# CW_Encoder.net
KiCad netlist of a schematic drawn in EAGLE
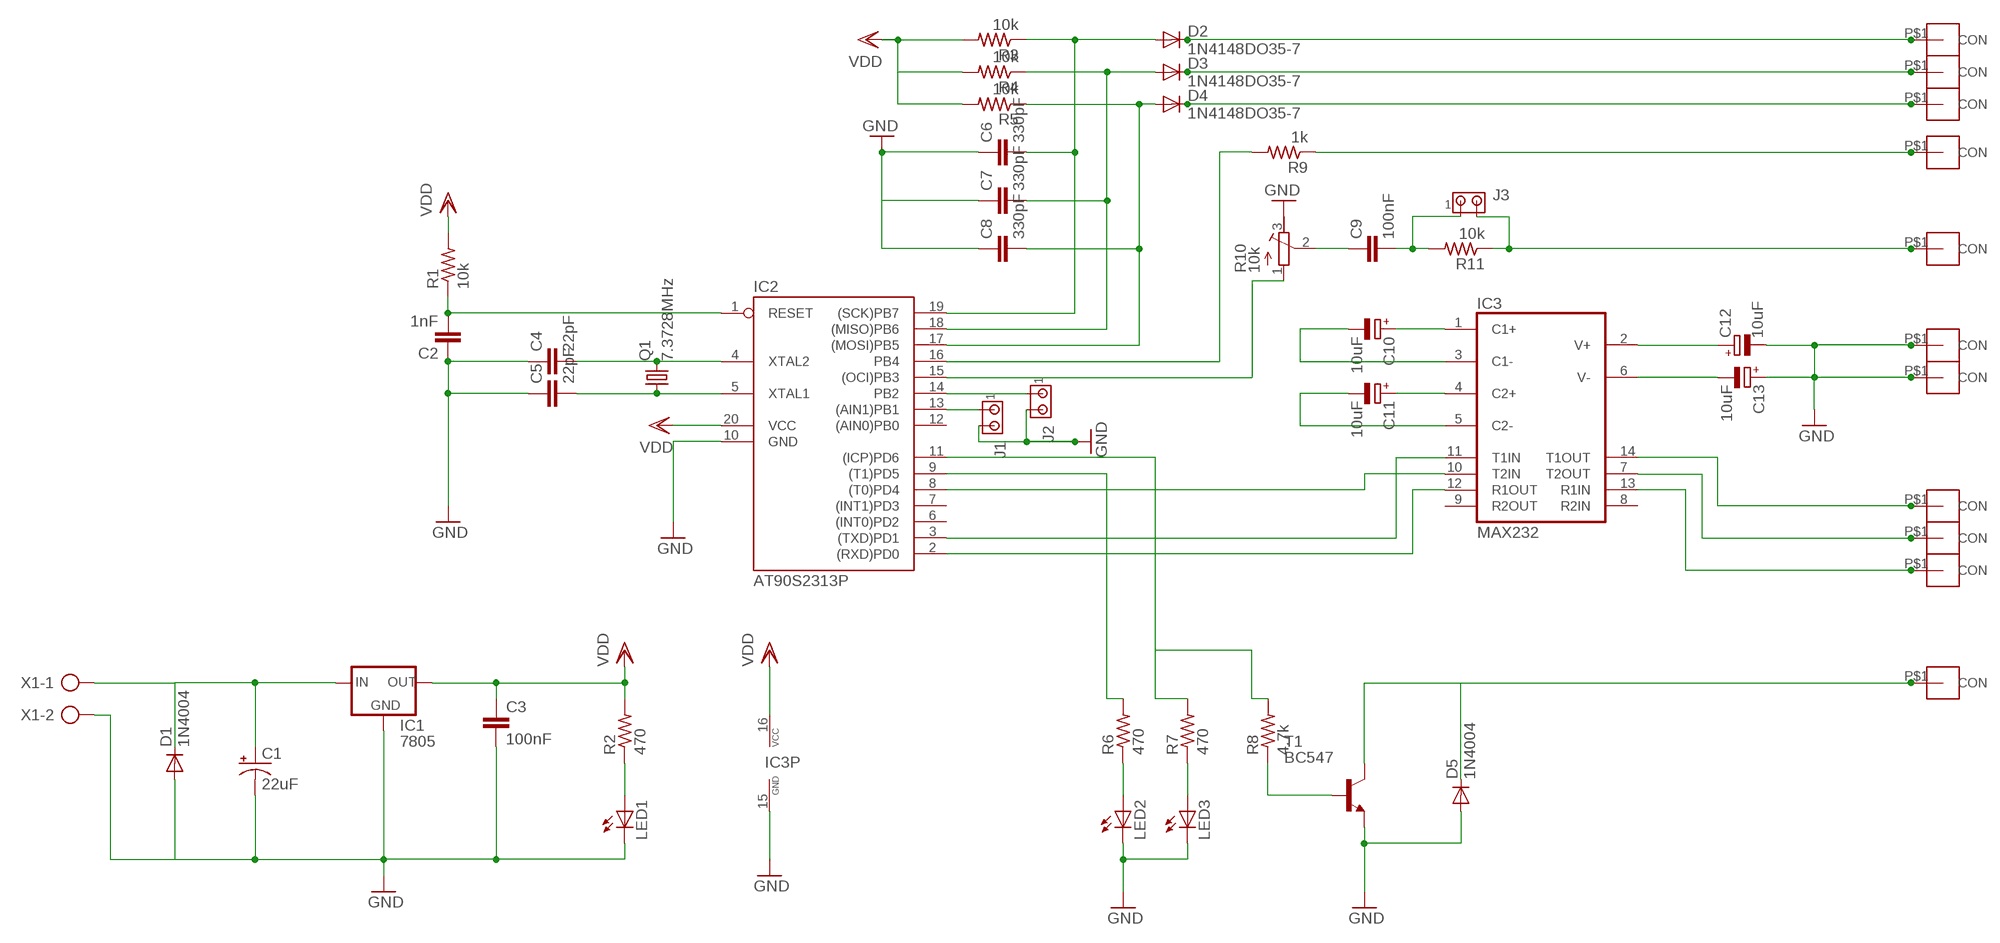
[diagram p0: schematic, sheet 2]

(export (version "E")
  (design (tool "Eeschema 10.0.6"))
  (components
    (comp (ref "C1")
      (value "22uF")
      (footprint "eagle-import:E2,5-4R")
      (libsource (lib "eagle-import") (part "CPOL-USE2.5-5V"))
    )
    (comp (ref "C2")
      (value "1nF")
      (footprint "eagle-import:C025-024X044")
      (libsource (lib "eagle-import") (part "C-EU025-024X044"))
    )
    (comp (ref "C3")
      (value "100nF")
      (footprint "eagle-import:C025-024X044")
      (libsource (lib "eagle-import") (part "C-EU025-024X044"))
    )
    (comp (ref "C4")
      (value "22pF")
      (footprint "eagle-import:C025-024X044")
      (libsource (lib "eagle-import") (part "C-EU025-024X044"))
    )
    (comp (ref "C5")
      (value "22pF")
      (footprint "eagle-import:C025-024X044")
      (libsource (lib "eagle-import") (part "C-EU025-024X044"))
    )
    (comp (ref "C6")
      (value "330pF")
      (footprint "eagle-import:C025-024X044")
      (libsource (lib "eagle-import") (part "C-EU025-024X044"))
    )
    (comp (ref "C7")
      (value "330pF")
      (footprint "eagle-import:C025-024X044")
      (libsource (lib "eagle-import") (part "C-EU025-024X044"))
    )
    (comp (ref "C8")
      (value "330pF")
      (footprint "eagle-import:C025-024X044")
      (libsource (lib "eagle-import") (part "C-EU025-024X044"))
    )
    (comp (ref "C9")
      (value "100nF")
      (footprint "eagle-import:C025-024X044")
      (libsource (lib "eagle-import") (part "C-EU025-024X044"))
    )
    (comp (ref "C10")
      (value "10uF")
      (footprint "eagle-import:B45181A")
      (libsource (lib "eagle-import") (part "CPOL-EUB45181A"))
    )
    (comp (ref "C11")
      (value "10uF")
      (footprint "eagle-import:B45181A")
      (libsource (lib "eagle-import") (part "CPOL-EUB45181A"))
    )
    (comp (ref "C12")
      (value "10uF")
      (footprint "eagle-import:B45181A")
      (libsource (lib "eagle-import") (part "CPOL-EUB45181A"))
    )
    (comp (ref "C13")
      (value "10uF")
      (footprint "eagle-import:B45181A")
      (libsource (lib "eagle-import") (part "CPOL-EUB45181A"))
    )
    (comp (ref "CTS")
      (value "CON1")
      (footprint "eagle-import:CON1")
      (libsource (lib "eagle-import") (part "CON1"))
    )
    (comp (ref "CWOUT")
      (value "CON1")
      (footprint "eagle-import:CON1")
      (libsource (lib "eagle-import") (part "CON1"))
    )
    (comp (ref "D1")
      (value "1N4004")
      (footprint "eagle-import:DO41-10")
      (libsource (lib "eagle-import") (part "1N4004"))
    )
    (comp (ref "D2")
      (value "1N4148DO35-7")
      (footprint "eagle-import:DO35-7")
      (libsource (lib "eagle-import") (part "1N4148DO35-7"))
    )
    (comp (ref "D3")
      (value "1N4148DO35-7")
      (footprint "eagle-import:DO35-7")
      (libsource (lib "eagle-import") (part "1N4148DO35-7"))
    )
    (comp (ref "D4")
      (value "1N4148DO35-7")
      (footprint "eagle-import:DO35-7")
      (libsource (lib "eagle-import") (part "1N4148DO35-7"))
    )
    (comp (ref "D5")
      (value "1N4004")
      (footprint "eagle-import:DO41-10")
      (libsource (lib "eagle-import") (part "1N4004"))
    )
    (comp (ref "GND")
      (value "CON1")
      (footprint "eagle-import:CON1")
      (libsource (lib "eagle-import") (part "CON1"))
    )
    (comp (ref "GND_")
      (value "CON1")
      (footprint "eagle-import:CON1")
      (libsource (lib "eagle-import") (part "CON1"))
    )
    (comp (ref "IC1")
      (value "7805")
      (footprint "eagle-import:78XXL")
      (libsource (lib "eagle-import") (part "78XXL"))
    )
    (comp (ref "IC2")
      (value "AT90S2313P")
      (footprint "eagle-import:DIL20")
      (libsource (lib "eagle-import") (part "AT90S2313P"))
    )
    (comp (ref "IC3")
      (value "MAX232")
      (footprint "eagle-import:DIL16")
      (fields (field (name "MF") "MAXIM") (field (name "MPN") "MAX232ACPE+"))
      (libsource (lib "eagle-import") (part "MAX232"))
    )
    (comp (ref "IN1")
      (value "CON1")
      (footprint "eagle-import:CON1")
      (libsource (lib "eagle-import") (part "CON1"))
    )
    (comp (ref "IN2")
      (value "CON1")
      (footprint "eagle-import:CON1")
      (libsource (lib "eagle-import") (part "CON1"))
    )
    (comp (ref "J1")
      (value "MTA02-100")
      (footprint "eagle-import:10X02MTA")
      (libsource (lib "eagle-import") (part "MTA02-100"))
    )
    (comp (ref "J2")
      (value "MTA02-100")
      (footprint "eagle-import:10X02MTA")
      (libsource (lib "eagle-import") (part "MTA02-100"))
    )
    (comp (ref "J3")
      (value "MTA02-100")
      (footprint "eagle-import:10X02MTA")
      (libsource (lib "eagle-import") (part "MTA02-100"))
    )
    (comp (ref "LED1")
      (value "LED5MM")
      (footprint "eagle-import:LED5MM")
      (libsource (lib "eagle-import") (part "LED5MM"))
    )
    (comp (ref "LED2")
      (value "LED5MM")
      (footprint "eagle-import:LED5MM")
      (libsource (lib "eagle-import") (part "LED5MM"))
    )
    (comp (ref "LED3")
      (value "LED5MM")
      (footprint "eagle-import:LED5MM")
      (libsource (lib "eagle-import") (part "LED5MM"))
    )
    (comp (ref "POSAGOUT")
      (value "CON1")
      (footprint "eagle-import:CON1")
      (libsource (lib "eagle-import") (part "CON1"))
    )
    (comp (ref "PTT")
      (value "CON1")
      (footprint "eagle-import:CON1")
      (libsource (lib "eagle-import") (part "CON1"))
    )
    (comp (ref "Q1")
      (value "7.3728MHz")
      (footprint "eagle-import:HC49_S")
      (libsource (lib "eagle-import") (part "CRYSTALHC49S"))
    )
    (comp (ref "R1")
      (value "10k")
      (footprint "eagle-import:0204_7")
      (libsource (lib "eagle-import") (part "R-US_0204/7"))
    )
    (comp (ref "R2")
      (value "470")
      (footprint "eagle-import:0204_7")
      (libsource (lib "eagle-import") (part "R-US_0204/7"))
    )
    (comp (ref "R3")
      (value "10k")
      (footprint "eagle-import:0204_7")
      (libsource (lib "eagle-import") (part "R-US_0204/7"))
    )
    (comp (ref "R4")
      (value "10k")
      (footprint "eagle-import:0204_7")
      (libsource (lib "eagle-import") (part "R-US_0204/7"))
    )
    (comp (ref "R5")
      (value "10k")
      (footprint "eagle-import:0204_7")
      (libsource (lib "eagle-import") (part "R-US_0204/7"))
    )
    (comp (ref "R6")
      (value "470")
      (footprint "eagle-import:0204_7")
      (libsource (lib "eagle-import") (part "R-US_0204/7"))
    )
    (comp (ref "R7")
      (value "470")
      (footprint "eagle-import:0204_7")
      (libsource (lib "eagle-import") (part "R-US_0204/7"))
    )
    (comp (ref "R8")
      (value "4.7k")
      (footprint "eagle-import:0204_7")
      (libsource (lib "eagle-import") (part "R-US_0204/7"))
    )
    (comp (ref "R9")
      (value "1k")
      (footprint "eagle-import:0204_7")
      (libsource (lib "eagle-import") (part "R-US_0204/7"))
    )
    (comp (ref "R10")
      (value "10k")
      (footprint "eagle-import:RTRIM3339P")
      (libsource (lib "eagle-import") (part "R-TRIMM3339P"))
    )
    (comp (ref "R11")
      (value "10k")
      (footprint "eagle-import:0204_7")
      (libsource (lib "eagle-import") (part "R-US_0204/7"))
    )
    (comp (ref "T1")
      (value "BC547")
      (footprint "eagle-import:TO92")
      (libsource (lib "eagle-import") (part "BC547"))
    )
    (comp (ref "TX")
      (value "tx")
      (footprint "eagle-import:CON1")
      (libsource (lib "eagle-import") (part "CON1"))
    )
    (comp (ref "TXD")
      (value "CON1")
      (footprint "eagle-import:CON1")
      (libsource (lib "eagle-import") (part "CON1"))
    )
    (comp (ref "U$1")
      (value "CON1")
      (footprint "eagle-import:CON1")
      (libsource (lib "eagle-import") (part "CON1"))
    )
    (comp (ref "X1")
      (value "AK300/2")
      (footprint "eagle-import:AK300_2")
      (libsource (lib "eagle-import") (part "AK300/2"))
    )
  )
  (nets
    (net (code "1") (name "GND") (class "Default")
      (node (ref "C1") (pin "-") (pinfunction "-_-") (pintype "passive"))
      (node (ref "C12") (pin "-") (pinfunction "-_-") (pintype "passive"))
      (node (ref "C13") (pin "+") (pinfunction "+_+") (pintype "passive"))
      (node (ref "C2") (pin "1") (pinfunction "1_1") (pintype "passive"))
      (node (ref "C3") (pin "2") (pinfunction "2_2") (pintype "passive"))
      (node (ref "C4") (pin "1") (pinfunction "1_1") (pintype "passive"))
      (node (ref "C5") (pin "1") (pinfunction "1_1") (pintype "passive"))
      (node (ref "C6") (pin "1") (pinfunction "1_1") (pintype "passive"))
      (node (ref "C7") (pin "1") (pinfunction "1_1") (pintype "passive"))
      (node (ref "C8") (pin "1") (pinfunction "1_1") (pintype "passive"))
      (node (ref "D1") (pin "A") (pinfunction "A_A") (pintype "passive"))
      (node (ref "D5") (pin "A") (pinfunction "A_A") (pintype "passive"))
      (node (ref "GND") (pin "P$1") (pinfunction "CON_P$1") (pintype "bidirectional"))
      (node (ref "GND_") (pin "P$1") (pinfunction "CON_P$1") (pintype "bidirectional"))
      (node (ref "IC1") (pin "GND") (pinfunction "GND_GND") (pintype "input"))
      (node (ref "IC2") (pin "10") (pinfunction "GND_10") (pintype "power_in"))
      (node (ref "IC3") (pin "15") (pinfunction "GND_15") (pintype "power_in"))
      (node (ref "J1") (pin "2") (pinfunction "2_2") (pintype "passive"))
      (node (ref "J2") (pin "2") (pinfunction "2_2") (pintype "passive"))
      (node (ref "LED1") (pin "K") (pinfunction "C_K") (pintype "passive"))
      (node (ref "LED2") (pin "K") (pinfunction "C_K") (pintype "passive"))
      (node (ref "LED3") (pin "K") (pinfunction "C_K") (pintype "passive"))
      (node (ref "R10") (pin "3") (pinfunction "A_3") (pintype "passive"))
      (node (ref "T1") (pin "1") (pinfunction "E_1") (pintype "passive"))
      (node (ref "X1") (pin "2") (pinfunction "KL_2") (pintype "passive"))
    )
    (net (code "2") (name "Net-(C9-Pad2)") (class "Default")
      (node (ref "C9") (pin "2") (pinfunction "2_2") (pintype "passive"))
      (node (ref "J3") (pin "1") (pinfunction "1_1") (pintype "passive"))
      (node (ref "R11") (pin "2") (pinfunction "2_2") (pintype "passive"))
    )
    (net (code "3") (name "Net-(CTS-CON)") (class "Default")
      (node (ref "CTS") (pin "P$1") (pinfunction "CON_P$1") (pintype "bidirectional"))
      (node (ref "IC3") (pin "7") (pinfunction "T2OUT_7") (pintype "output"))
    )
    (net (code "4") (name "Net-(CWOUT-CON)") (class "Default")
      (node (ref "CWOUT") (pin "P$1") (pinfunction "CON_P$1") (pintype "bidirectional"))
      (node (ref "J3") (pin "2") (pinfunction "2_2") (pintype "passive"))
      (node (ref "R11") (pin "1") (pinfunction "1_1") (pintype "passive"))
    )
    (net (code "5") (name "Net-(IC2-(AIN1)PB1)") (class "Default")
      (node (ref "IC2") (pin "13") (pinfunction "(AIN1)PB1_13") (pintype "bidirectional"))
      (node (ref "J1") (pin "1") (pinfunction "1_1") (pintype "passive"))
    )
    (net (code "6") (name "Net-(IC2-(ICP)PD6)") (class "Default")
      (node (ref "IC2") (pin "11") (pinfunction "(ICP)PD6_11") (pintype "bidirectional"))
      (node (ref "R7") (pin "2") (pinfunction "2_2") (pintype "passive"))
      (node (ref "R8") (pin "2") (pinfunction "2_2") (pintype "passive"))
    )
    (net (code "7") (name "Net-(IC2-(MISO)PB6)") (class "Default")
      (node (ref "C7") (pin "2") (pinfunction "2_2") (pintype "passive"))
      (node (ref "D3") (pin "A") (pinfunction "A_A") (pintype "passive"))
      (node (ref "IC2") (pin "18") (pinfunction "(MISO)PB6_18") (pintype "bidirectional"))
      (node (ref "R4") (pin "1") (pinfunction "1_1") (pintype "passive"))
    )
    (net (code "8") (name "Net-(IC2-(MOSI)PB5)") (class "Default")
      (node (ref "C8") (pin "2") (pinfunction "2_2") (pintype "passive"))
      (node (ref "D4") (pin "A") (pinfunction "A_A") (pintype "passive"))
      (node (ref "IC2") (pin "17") (pinfunction "(MOSI)PB5_17") (pintype "bidirectional"))
      (node (ref "R5") (pin "1") (pinfunction "1_1") (pintype "passive"))
    )
    (net (code "9") (name "Net-(IC2-(OCI)PB3)") (class "Default")
      (node (ref "IC2") (pin "15") (pinfunction "(OCI)PB3_15") (pintype "bidirectional"))
      (node (ref "R10") (pin "1") (pinfunction "E_1") (pintype "passive"))
    )
    (net (code "10") (name "Net-(IC2-(RXD)PD0)") (class "Default")
      (node (ref "IC2") (pin "2") (pinfunction "(RXD)PD0_2") (pintype "bidirectional"))
      (node (ref "IC3") (pin "12") (pinfunction "R1OUT_12") (pintype "output"))
    )
    (net (code "11") (name "Net-(IC2-(SCK)PB7)") (class "Default")
      (node (ref "C6") (pin "2") (pinfunction "2_2") (pintype "passive"))
      (node (ref "D2") (pin "A") (pinfunction "A_A") (pintype "passive"))
      (node (ref "IC2") (pin "19") (pinfunction "(SCK)PB7_19") (pintype "bidirectional"))
      (node (ref "R3") (pin "1") (pinfunction "1_1") (pintype "passive"))
    )
    (net (code "12") (name "Net-(IC2-(T0)PD4)") (class "Default")
      (node (ref "IC2") (pin "8") (pinfunction "(T0)PD4_8") (pintype "bidirectional"))
      (node (ref "IC3") (pin "10") (pinfunction "T2IN_10") (pintype "input"))
    )
    (net (code "13") (name "Net-(IC2-(T1)PD5)") (class "Default")
      (node (ref "IC2") (pin "9") (pinfunction "(T1)PD5_9") (pintype "bidirectional"))
      (node (ref "R6") (pin "2") (pinfunction "2_2") (pintype "passive"))
    )
    (net (code "14") (name "Net-(IC2-(TXD)PD1)") (class "Default")
      (node (ref "IC2") (pin "3") (pinfunction "(TXD)PD1_3") (pintype "bidirectional"))
      (node (ref "IC3") (pin "11") (pinfunction "T1IN_11") (pintype "input"))
    )
    (net (code "15") (name "Net-(IC2-PB2)") (class "Default")
      (node (ref "IC2") (pin "14") (pinfunction "PB2_14") (pintype "bidirectional"))
      (node (ref "J2") (pin "1") (pinfunction "1_1") (pintype "passive"))
    )
    (net (code "16") (name "Net-(IC2-PB4)") (class "Default")
      (node (ref "IC2") (pin "16") (pinfunction "PB4_16") (pintype "bidirectional"))
      (node (ref "R9") (pin "2") (pinfunction "2_2") (pintype "passive"))
    )
    (net (code "17") (name "Net-(IC2-RESET)") (class "Default")
      (node (ref "C2") (pin "2") (pinfunction "2_2") (pintype "passive"))
      (node (ref "IC2") (pin "1") (pinfunction "RESET_1") (pintype "bidirectional"))
      (node (ref "R1") (pin "1") (pinfunction "1_1") (pintype "passive"))
    )
    (net (code "18") (name "Net-(IC2-XTAL1)") (class "Default")
      (node (ref "C5") (pin "2") (pinfunction "2_2") (pintype "passive"))
      (node (ref "IC2") (pin "5") (pinfunction "XTAL1_5") (pintype "bidirectional"))
      (node (ref "Q1") (pin "1") (pinfunction "1_1") (pintype "passive"))
    )
    (net (code "19") (name "Net-(IC2-XTAL2)") (class "Default")
      (node (ref "C4") (pin "2") (pinfunction "2_2") (pintype "passive"))
      (node (ref "IC2") (pin "4") (pinfunction "XTAL2_4") (pintype "bidirectional"))
      (node (ref "Q1") (pin "2") (pinfunction "2_2") (pintype "passive"))
    )
    (net (code "20") (name "Net-(IC3A-C1+)") (class "Default")
      (node (ref "C10") (pin "+") (pinfunction "+_+") (pintype "passive"))
      (node (ref "IC3") (pin "1") (pinfunction "C1+_1") (pintype "bidirectional"))
    )
    (net (code "21") (name "Net-(IC3A-C1-)") (class "Default")
      (node (ref "C10") (pin "-") (pinfunction "-_-") (pintype "passive"))
      (node (ref "IC3") (pin "3") (pinfunction "C1-_3") (pintype "bidirectional"))
    )
    (net (code "22") (name "Net-(IC3A-C2+)") (class "Default")
      (node (ref "C11") (pin "+") (pinfunction "+_+") (pintype "passive"))
      (node (ref "IC3") (pin "4") (pinfunction "C2+_4") (pintype "bidirectional"))
    )
    (net (code "23") (name "Net-(IC3A-C2-)") (class "Default")
      (node (ref "C11") (pin "-") (pinfunction "-_-") (pintype "passive"))
      (node (ref "IC3") (pin "5") (pinfunction "C2-_5") (pintype "bidirectional"))
    )
    (net (code "24") (name "Net-(IC3A-R1IN)") (class "Default")
      (node (ref "IC3") (pin "13") (pinfunction "R1IN_13") (pintype "input"))
      (node (ref "U$1") (pin "P$1") (pinfunction "CON_P$1") (pintype "bidirectional"))
    )
    (net (code "25") (name "Net-(IC3A-T1OUT)") (class "Default")
      (node (ref "IC3") (pin "14") (pinfunction "T1OUT_14") (pintype "output"))
      (node (ref "TXD") (pin "P$1") (pinfunction "CON_P$1") (pintype "bidirectional"))
    )
    (net (code "26") (name "Net-(IC3A-V+)") (class "Default")
      (node (ref "C12") (pin "+") (pinfunction "+_+") (pintype "passive"))
      (node (ref "IC3") (pin "2") (pinfunction "V+_2") (pintype "bidirectional"))
    )
    (net (code "27") (name "Net-(IC3A-V-)") (class "Default")
      (node (ref "C13") (pin "-") (pinfunction "-_-") (pintype "passive"))
      (node (ref "IC3") (pin "6") (pinfunction "V-_6") (pintype "bidirectional"))
    )
    (net (code "28") (name "Net-(IN1-CON)") (class "Default")
      (node (ref "D3") (pin "C") (pinfunction "C_C") (pintype "passive"))
      (node (ref "IN1") (pin "P$1") (pinfunction "CON_P$1") (pintype "bidirectional"))
    )
    (net (code "29") (name "Net-(IN2-CON)") (class "Default")
      (node (ref "D4") (pin "C") (pinfunction "C_C") (pintype "passive"))
      (node (ref "IN2") (pin "P$1") (pinfunction "CON_P$1") (pintype "bidirectional"))
    )
    (net (code "30") (name "Net-(LED1-PadA)") (class "Default")
      (node (ref "LED1") (pin "A") (pinfunction "A_A") (pintype "passive"))
      (node (ref "R2") (pin "1") (pinfunction "1_1") (pintype "passive"))
    )
    (net (code "31") (name "Net-(LED2-PadA)") (class "Default")
      (node (ref "LED2") (pin "A") (pinfunction "A_A") (pintype "passive"))
      (node (ref "R6") (pin "1") (pinfunction "1_1") (pintype "passive"))
    )
    (net (code "32") (name "Net-(LED3-PadA)") (class "Default")
      (node (ref "LED3") (pin "A") (pinfunction "A_A") (pintype "passive"))
      (node (ref "R7") (pin "1") (pinfunction "1_1") (pintype "passive"))
    )
    (net (code "33") (name "Net-(POSAGOUT-CON)") (class "Default")
      (node (ref "POSAGOUT") (pin "P$1") (pinfunction "CON_P$1") (pintype "bidirectional"))
      (node (ref "R9") (pin "1") (pinfunction "1_1") (pintype "passive"))
    )
    (net (code "34") (name "Net-(PTT-CON)") (class "Default")
      (node (ref "D5") (pin "C") (pinfunction "C_C") (pintype "passive"))
      (node (ref "PTT") (pin "P$1") (pinfunction "CON_P$1") (pintype "bidirectional"))
      (node (ref "T1") (pin "3") (pinfunction "C_3") (pintype "passive"))
    )
    (net (code "35") (name "Net-(R10-S)") (class "Default")
      (node (ref "C9") (pin "1") (pinfunction "1_1") (pintype "passive"))
      (node (ref "R10") (pin "2") (pinfunction "S_2") (pintype "passive"))
    )
    (net (code "36") (name "Net-(T1-B)") (class "Default")
      (node (ref "R8") (pin "1") (pinfunction "1_1") (pintype "passive"))
      (node (ref "T1") (pin "2") (pinfunction "B_2") (pintype "passive"))
    )
    (net (code "37") (name "Net-(TX-CON)") (class "Default")
      (node (ref "D2") (pin "C") (pinfunction "C_C") (pintype "passive"))
      (node (ref "TX") (pin "P$1") (pinfunction "CON_P$1") (pintype "bidirectional"))
    )
    (net (code "38") (name "Net-(X1A-KL)") (class "Default")
      (node (ref "C1") (pin "+") (pinfunction "+_+") (pintype "passive"))
      (node (ref "D1") (pin "C") (pinfunction "C_C") (pintype "passive"))
      (node (ref "IC1") (pin "IN") (pinfunction "IN_IN") (pintype "input"))
      (node (ref "X1") (pin "1") (pinfunction "KL_1") (pintype "passive"))
    )
    (net (code "39") (name "VDD") (class "Default")
      (node (ref "C3") (pin "1") (pinfunction "1_1") (pintype "passive"))
      (node (ref "IC1") (pin "OUT") (pinfunction "OUT_OUT") (pintype "passive"))
      (node (ref "IC2") (pin "20") (pinfunction "VCC_20") (pintype "power_in"))
      (node (ref "IC3") (pin "16") (pinfunction "VCC_16") (pintype "power_in"))
      (node (ref "R1") (pin "2") (pinfunction "2_2") (pintype "passive"))
      (node (ref "R2") (pin "2") (pinfunction "2_2") (pintype "passive"))
      (node (ref "R3") (pin "2") (pinfunction "2_2") (pintype "passive"))
      (node (ref "R4") (pin "2") (pinfunction "2_2") (pintype "passive"))
      (node (ref "R5") (pin "2") (pinfunction "2_2") (pintype "passive"))
    )
    (net (code "40") (name "unconnected-(IC2-(AIN0)PB0-Pad12)") (class "Default")
      (node (ref "IC2") (pin "12") (pinfunction "(AIN0)PB0_12") (pintype "bidirectional"))
    )
    (net (code "41") (name "unconnected-(IC2-(INT0)PD2-Pad6)") (class "Default")
      (node (ref "IC2") (pin "6") (pinfunction "(INT0)PD2_6") (pintype "bidirectional"))
    )
    (net (code "42") (name "unconnected-(IC2-(INT1)PD3-Pad7)") (class "Default")
      (node (ref "IC2") (pin "7") (pinfunction "(INT1)PD3_7") (pintype "bidirectional"))
    )
    (net (code "43") (name "unconnected-(IC3A-R2IN-Pad8)") (class "Default")
      (node (ref "IC3") (pin "8") (pinfunction "R2IN_8") (pintype "input"))
    )
    (net (code "44") (name "unconnected-(IC3A-R2OUT-Pad9)") (class "Default")
      (node (ref "IC3") (pin "9") (pinfunction "R2OUT_9") (pintype "output"))
    )
  )
)
